# openSX70-dongle_v3-2.net
KiCad netlist of a schematic drawn in EAGLE
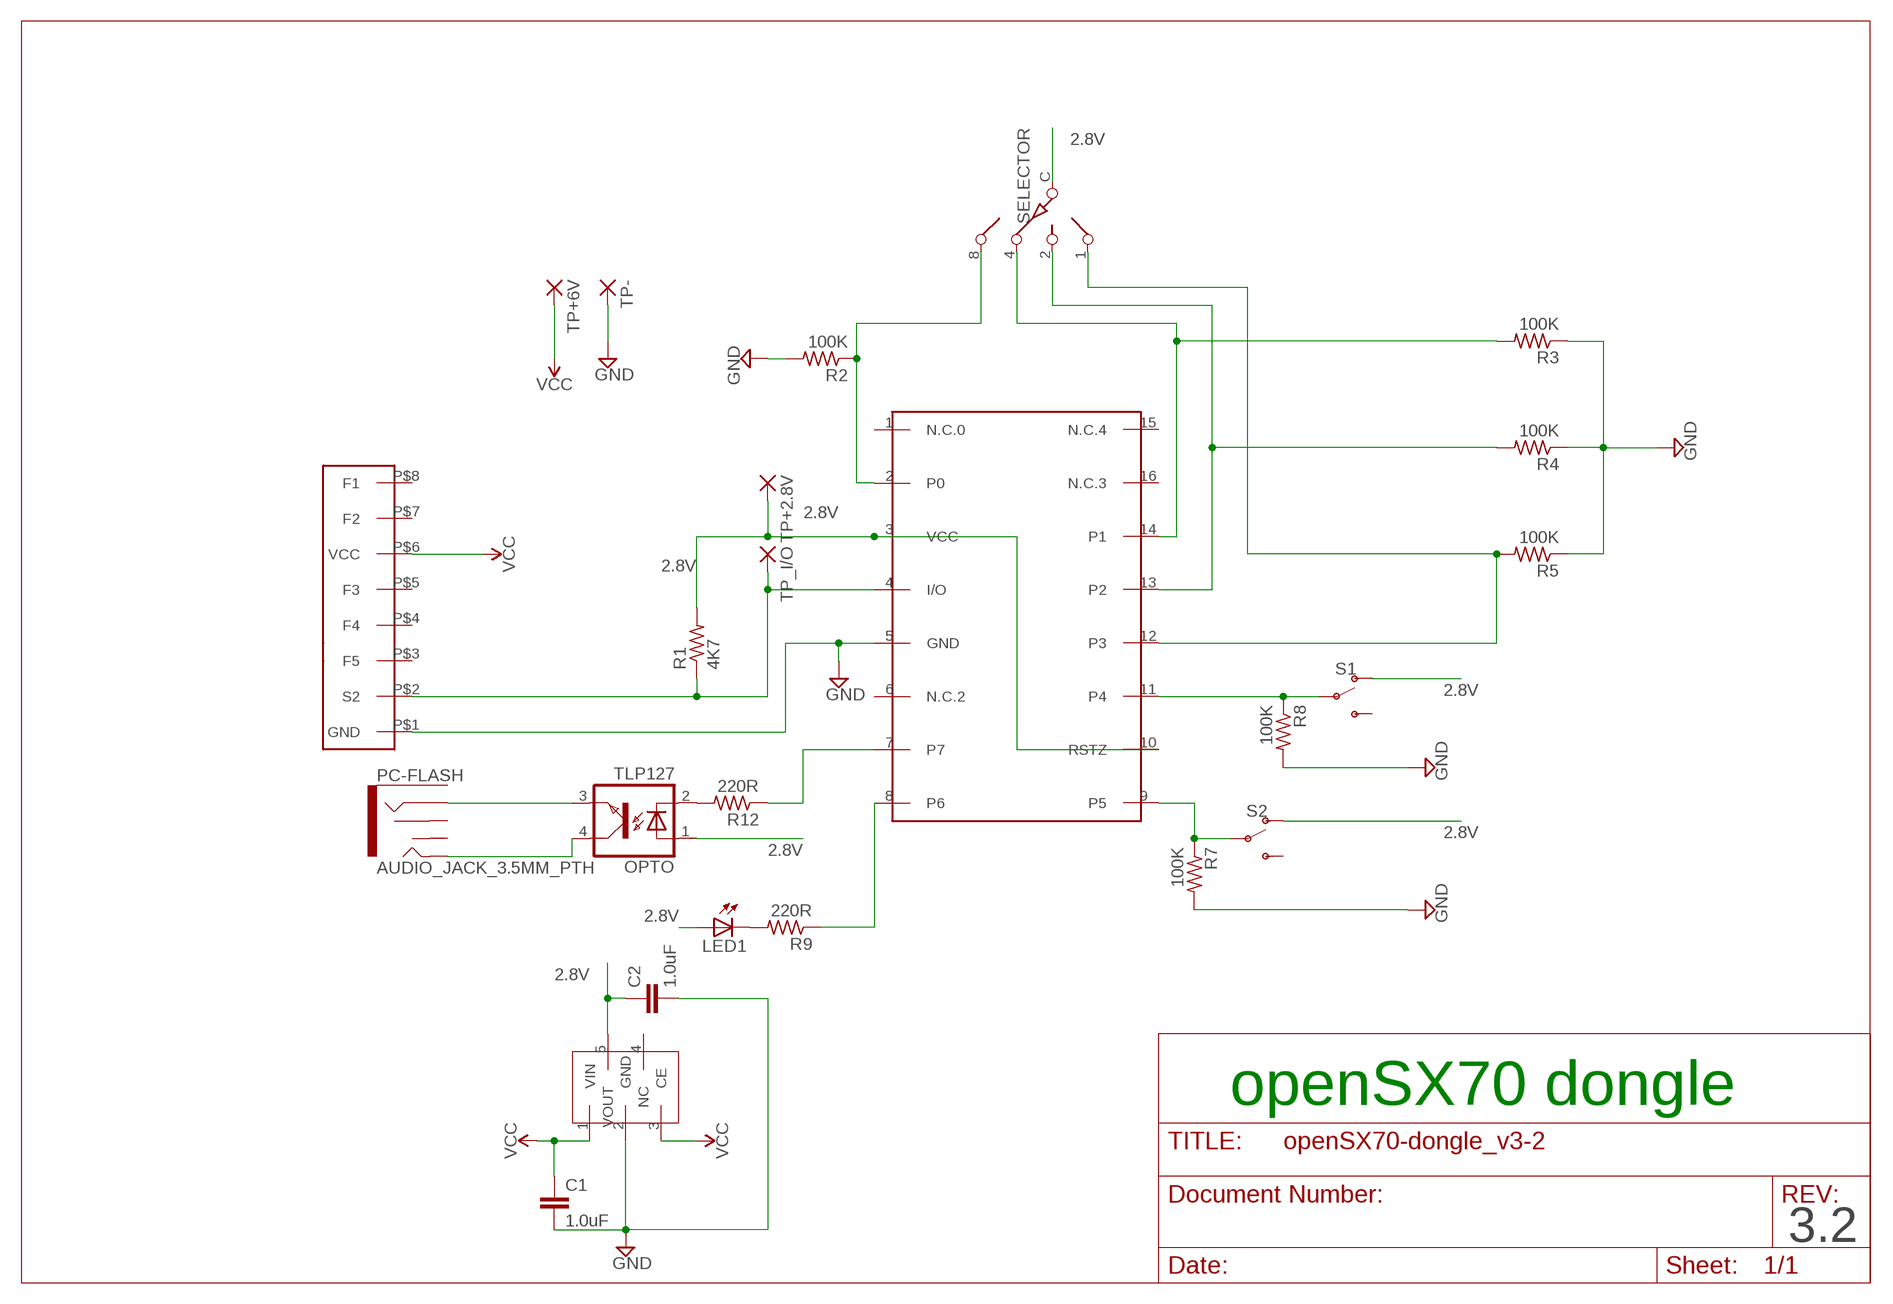
[diagram p0: schematic, sheet 1]

(export (version "E")
  (design (tool "Eeschema 10.0.6"))
  (components
    (comp (ref "C1")
      (value "1.0uF")
      (footprint "eagle-import:C0603")
      (libsource (lib "eagle-import") (part "C-EUC0603"))
    )
    (comp (ref "C2")
      (value "1.0uF")
      (footprint "eagle-import:C0603")
      (libsource (lib "eagle-import") (part "C-EUC0603"))
    )
    (comp (ref "DS2408")
      (value "DS2408")
      (footprint "eagle-import:SO16")
      (libsource (lib "eagle-import") (part "DS2408"))
    )
    (comp (ref "LED1")
      (value "LED3MM")
      (footprint "eagle-import:LED3MM")
      (libsource (lib "eagle-import") (part "LED3MM"))
    )
    (comp (ref "OPTO")
      (value "TLP127")
      (footprint "eagle-import:SO-4")
      (libsource (lib "eagle-import") (part "TLP127"))
    )
    (comp (ref "PC-FLASH")
      (value "AUDIO_JACK_3.5MM_PTH")
      (footprint "eagle-import:AUDIO-JACK")
      (libsource (lib "eagle-import") (part "AUDIO_JACK_3.5MM_PTH"))
    )
    (comp (ref "R1")
      (value "4K7")
      (footprint "eagle-import:M0805")
      (libsource (lib "eagle-import") (part "R-US_M0805"))
    )
    (comp (ref "R2")
      (value "100K")
      (footprint "eagle-import:M0805")
      (libsource (lib "eagle-import") (part "R-US_M0805"))
    )
    (comp (ref "R3")
      (value "100K")
      (footprint "eagle-import:M0805")
      (libsource (lib "eagle-import") (part "R-US_M0805"))
    )
    (comp (ref "R4")
      (value "100K")
      (footprint "eagle-import:M0805")
      (libsource (lib "eagle-import") (part "R-US_M0805"))
    )
    (comp (ref "R5")
      (value "100K")
      (footprint "eagle-import:M0805")
      (libsource (lib "eagle-import") (part "R-US_M0805"))
    )
    (comp (ref "R7")
      (value "100K")
      (footprint "eagle-import:M0805")
      (libsource (lib "eagle-import") (part "R-US_M0805"))
    )
    (comp (ref "R8")
      (value "100K")
      (footprint "eagle-import:M0805")
      (libsource (lib "eagle-import") (part "R-US_M0805"))
    )
    (comp (ref "R9")
      (value "220R")
      (footprint "eagle-import:M0805")
      (libsource (lib "eagle-import") (part "R-US_M0805"))
    )
    (comp (ref "R12")
      (value "220R")
      (footprint "eagle-import:M0805")
      (libsource (lib "eagle-import") (part "R-US_M0805"))
    )
    (comp (ref "REG")
      (value "NCP4688")
      (footprint "eagle-import:SOT-23-5")
      (libsource (lib "eagle-import") (part "NCP4688"))
    )
    (comp (ref "S1")
      (value "SWITCH-SPDT-SMD-RIGHT-ANGLE")
      (footprint "eagle-import:SWITCH_SPST_SMD_A")
      (libsource (lib "eagle-import") (part "SWITCH-SPDT-SMD-RIGHT-ANGLE"))
    )
    (comp (ref "S2")
      (value "SWITCH-SPDT-SMD-RIGHT-ANGLE")
      (footprint "eagle-import:SWITCH_SPST_SMD_A")
      (libsource (lib "eagle-import") (part "SWITCH-SPDT-SMD-RIGHT-ANGLE"))
    )
    (comp (ref "SELECTOR")
      (value "SW-C16")
      (footprint "eagle-import:SW-C16")
      (libsource (lib "eagle-import") (part "SW-C16"))
    )
    (comp (ref "TP+2.8V")
      (value "SMD2")
      (footprint "eagle-import:SMD1,27-2,54")
      (libsource (lib "eagle-import") (part "SMD2"))
    )
    (comp (ref "TP+6V")
      (value "SMD2")
      (footprint "eagle-import:SMD1,27-2,54")
      (libsource (lib "eagle-import") (part "SMD2"))
    )
    (comp (ref "TP-")
      (value "SMD2")
      (footprint "eagle-import:SMD1,27-2,54")
      (libsource (lib "eagle-import") (part "SMD2"))
    )
    (comp (ref "TP_I/O")
      (value "SMD2")
      (footprint "eagle-import:SMD1,27-2,54")
      (libsource (lib "eagle-import") (part "SMD2"))
    )
    (comp (ref "U$1")
      (value "FLASH-EDGE-CONNECTOR")
      (footprint "eagle-import:FLASH-EDGE-8")
      (libsource (lib "eagle-import") (part "FLASH-EDGE-CONNECTOR"))
    )
  )
  (nets
    (net (code "1") (name "/2.8V") (class "Default")
      (node (ref "C2") (pin "1") (pinfunction "1_1") (pintype "passive"))
      (node (ref "DS2408") (pin "10") (pinfunction "RSTZ_10") (pintype "bidirectional"))
      (node (ref "DS2408") (pin "3") (pinfunction "VCC_3") (pintype "bidirectional"))
      (node (ref "LED1") (pin "A") (pinfunction "A_A") (pintype "passive"))
      (node (ref "OPTO") (pin "1") (pinfunction "A_1") (pintype "passive"))
      (node (ref "R1") (pin "2") (pinfunction "2_2") (pintype "passive"))
      (node (ref "REG") (pin "5") (pinfunction "VOUT_5") (pintype "bidirectional"))
      (node (ref "S1") (pin "1") (pinfunction "O_1") (pintype "passive"))
      (node (ref "S2") (pin "1") (pinfunction "O_1") (pintype "passive"))
      (node (ref "SELECTOR") (pin "C") (pinfunction "C_C") (pintype "passive"))
      (node (ref "TP+2.8V") (pin "1") (pinfunction "P_1") (pintype "passive"))
    )
    (net (code "2") (name "GND") (class "Default")
      (node (ref "C1") (pin "2") (pinfunction "2_2") (pintype "passive"))
      (node (ref "C2") (pin "2") (pinfunction "2_2") (pintype "passive"))
      (node (ref "DS2408") (pin "5") (pinfunction "GND_5") (pintype "bidirectional"))
      (node (ref "R2") (pin "2") (pinfunction "2_2") (pintype "passive"))
      (node (ref "R3") (pin "1") (pinfunction "1_1") (pintype "passive"))
      (node (ref "R4") (pin "1") (pinfunction "1_1") (pintype "passive"))
      (node (ref "R5") (pin "1") (pinfunction "1_1") (pintype "passive"))
      (node (ref "R7") (pin "2") (pinfunction "2_2") (pintype "passive"))
      (node (ref "R8") (pin "2") (pinfunction "2_2") (pintype "passive"))
      (node (ref "REG") (pin "2") (pinfunction "GND_2") (pintype "bidirectional"))
      (node (ref "TP-") (pin "1") (pinfunction "P_1") (pintype "passive"))
      (node (ref "U$1") (pin "P$1") (pinfunction "GND_P$1") (pintype "bidirectional"))
    )
    (net (code "3") (name "Net-(DS2408-I{slash}O)") (class "Default")
      (node (ref "DS2408") (pin "4") (pinfunction "I/O_4") (pintype "bidirectional"))
      (node (ref "R1") (pin "1") (pinfunction "1_1") (pintype "passive"))
      (node (ref "TP_I/O") (pin "1") (pinfunction "P_1") (pintype "passive"))
      (node (ref "U$1") (pin "P$2") (pinfunction "S2_P$2") (pintype "bidirectional"))
    )
    (net (code "4") (name "Net-(DS2408-P0)") (class "Default")
      (node (ref "DS2408") (pin "2") (pinfunction "P0_2") (pintype "bidirectional"))
      (node (ref "R2") (pin "1") (pinfunction "1_1") (pintype "passive"))
      (node (ref "SELECTOR") (pin "8") (pinfunction "8_8") (pintype "passive"))
    )
    (net (code "5") (name "Net-(DS2408-P1)") (class "Default")
      (node (ref "DS2408") (pin "14") (pinfunction "P1_14") (pintype "bidirectional"))
      (node (ref "R3") (pin "2") (pinfunction "2_2") (pintype "passive"))
      (node (ref "SELECTOR") (pin "4") (pinfunction "4_4") (pintype "passive"))
    )
    (net (code "6") (name "Net-(DS2408-P2)") (class "Default")
      (node (ref "DS2408") (pin "13") (pinfunction "P2_13") (pintype "bidirectional"))
      (node (ref "R4") (pin "2") (pinfunction "2_2") (pintype "passive"))
      (node (ref "SELECTOR") (pin "2") (pinfunction "2_2") (pintype "passive"))
    )
    (net (code "7") (name "Net-(DS2408-P3)") (class "Default")
      (node (ref "DS2408") (pin "12") (pinfunction "P3_12") (pintype "bidirectional"))
      (node (ref "R5") (pin "2") (pinfunction "2_2") (pintype "passive"))
      (node (ref "SELECTOR") (pin "1") (pinfunction "1_1") (pintype "passive"))
    )
    (net (code "8") (name "Net-(DS2408-P4)") (class "Default")
      (node (ref "DS2408") (pin "11") (pinfunction "P4_11") (pintype "bidirectional"))
      (node (ref "R8") (pin "1") (pinfunction "1_1") (pintype "passive"))
      (node (ref "S1") (pin "2") (pinfunction "P_2") (pintype "passive"))
    )
    (net (code "9") (name "Net-(DS2408-P5)") (class "Default")
      (node (ref "DS2408") (pin "9") (pinfunction "P5_9") (pintype "bidirectional"))
      (node (ref "R7") (pin "1") (pinfunction "1_1") (pintype "passive"))
      (node (ref "S2") (pin "2") (pinfunction "P_2") (pintype "passive"))
    )
    (net (code "10") (name "Net-(DS2408-P6)") (class "Default")
      (node (ref "DS2408") (pin "8") (pinfunction "P6_8") (pintype "bidirectional"))
      (node (ref "R9") (pin "1") (pinfunction "1_1") (pintype "passive"))
    )
    (net (code "11") (name "Net-(DS2408-P7)") (class "Default")
      (node (ref "DS2408") (pin "7") (pinfunction "P7_7") (pintype "bidirectional"))
      (node (ref "R12") (pin "1") (pinfunction "1_1") (pintype "passive"))
    )
    (net (code "12") (name "Net-(LED1-C)") (class "Default")
      (node (ref "LED1") (pin "K") (pinfunction "C_K") (pintype "passive"))
      (node (ref "R9") (pin "2") (pinfunction "2_2") (pintype "passive"))
    )
    (net (code "13") (name "Net-(OPTO-C)") (class "Default")
      (node (ref "OPTO") (pin "2") (pinfunction "C_2") (pintype "passive"))
      (node (ref "R12") (pin "2") (pinfunction "2_2") (pintype "passive"))
    )
    (net (code "14") (name "Net-(OPTO-COL)") (class "Default")
      (node (ref "OPTO") (pin "4") (pinfunction "COL_4") (pintype "passive"))
      (node (ref "PC-FLASH") (pin "TIP") (pinfunction "TIP_TIP") (pintype "bidirectional"))
    )
    (net (code "15") (name "Net-(OPTO-EMIT)") (class "Default")
      (node (ref "OPTO") (pin "3") (pinfunction "EMIT_3") (pintype "passive"))
      (node (ref "PC-FLASH") (pin "RING") (pinfunction "RING_RING") (pintype "bidirectional"))
    )
    (net (code "16") (name "VCC") (class "Default")
      (node (ref "C1") (pin "1") (pinfunction "1_1") (pintype "passive"))
      (node (ref "REG") (pin "1") (pinfunction "VIN_1") (pintype "bidirectional"))
      (node (ref "REG") (pin "3") (pinfunction "CE_3") (pintype "bidirectional"))
      (node (ref "TP+6V") (pin "1") (pinfunction "P_1") (pintype "passive"))
      (node (ref "U$1") (pin "P$6") (pinfunction "VCC_P$6") (pintype "bidirectional"))
    )
    (net (code "17") (name "unconnected-(DS2408-N.C.0-Pad1)") (class "Default")
      (node (ref "DS2408") (pin "1") (pinfunction "N.C.0_1") (pintype "bidirectional"))
    )
    (net (code "18") (name "unconnected-(DS2408-N.C.2-Pad6)") (class "Default")
      (node (ref "DS2408") (pin "6") (pinfunction "N.C.2_6") (pintype "bidirectional"))
    )
    (net (code "19") (name "unconnected-(DS2408-N.C.3-Pad16)") (class "Default")
      (node (ref "DS2408") (pin "16") (pinfunction "N.C.3_16") (pintype "bidirectional"))
    )
    (net (code "20") (name "unconnected-(DS2408-N.C.4-Pad15)") (class "Default")
      (node (ref "DS2408") (pin "15") (pinfunction "N.C.4_15") (pintype "bidirectional"))
    )
    (net (code "21") (name "unconnected-(PC-FLASH-PadRSH)") (class "Default")
      (node (ref "PC-FLASH") (pin "RSH") (pinfunction "RSH_RSH") (pintype "bidirectional"))
    )
    (net (code "22") (name "unconnected-(PC-FLASH-PadSLEEVE)") (class "Default")
      (node (ref "PC-FLASH") (pin "SLEEVE") (pinfunction "SLEEVE_SLEEVE") (pintype "bidirectional"))
    )
    (net (code "23") (name "unconnected-(PC-FLASH-PadTSH)") (class "Default")
      (node (ref "PC-FLASH") (pin "TSH") (pinfunction "TSH_TSH") (pintype "bidirectional"))
    )
    (net (code "24") (name "unconnected-(REG-NC-Pad4)") (class "Default")
      (node (ref "REG") (pin "4") (pinfunction "NC_4") (pintype "bidirectional"))
    )
    (net (code "25") (name "unconnected-(S1-S-Pad3)") (class "Default")
      (node (ref "S1") (pin "3") (pinfunction "S_3") (pintype "passive"))
    )
    (net (code "26") (name "unconnected-(S2-S-Pad3)") (class "Default")
      (node (ref "S2") (pin "3") (pinfunction "S_3") (pintype "passive"))
    )
    (net (code "27") (name "unconnected-(U$1-F1-PadP$8)") (class "Default")
      (node (ref "U$1") (pin "P$8") (pinfunction "F1_P$8") (pintype "bidirectional"))
    )
    (net (code "28") (name "unconnected-(U$1-F2-PadP$7)") (class "Default")
      (node (ref "U$1") (pin "P$7") (pinfunction "F2_P$7") (pintype "bidirectional"))
    )
    (net (code "29") (name "unconnected-(U$1-F3-PadP$5)") (class "Default")
      (node (ref "U$1") (pin "P$5") (pinfunction "F3_P$5") (pintype "bidirectional"))
    )
    (net (code "30") (name "unconnected-(U$1-F4-PadP$4)") (class "Default")
      (node (ref "U$1") (pin "P$4") (pinfunction "F4_P$4") (pintype "bidirectional"))
    )
    (net (code "31") (name "unconnected-(U$1-F5-PadP$3)") (class "Default")
      (node (ref "U$1") (pin "P$3") (pinfunction "F5_P$3") (pintype "bidirectional"))
    )
  )
)
